# ota.net
KiCad netlist of a schematic drawn in EAGLE
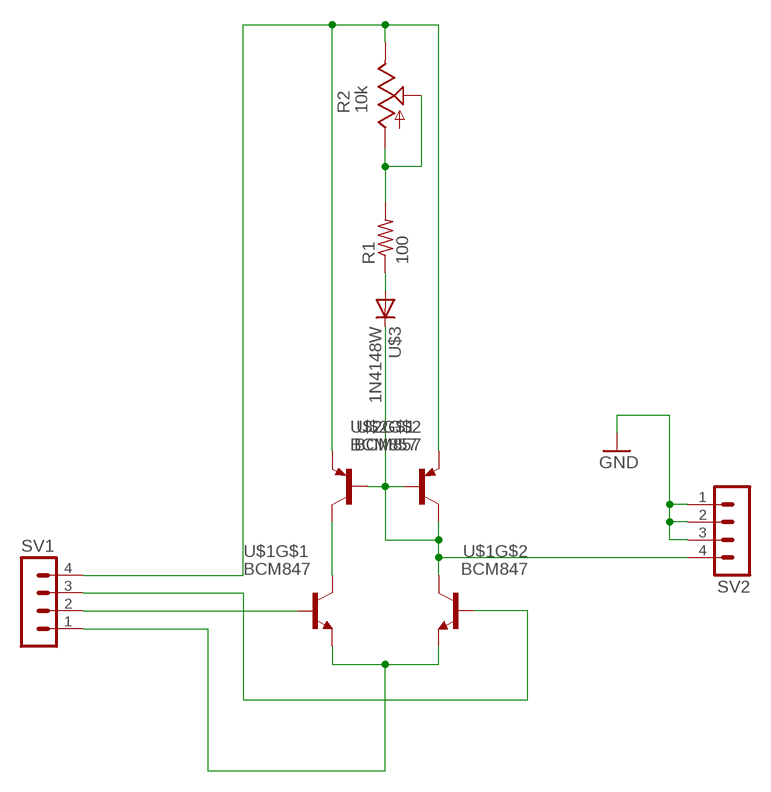
[diagram p0: schematic, sheet 1]

(export (version "E")
  (design (tool "Eeschema 10.0.6"))
  (components
    (comp (ref "R1")
      (value "100")
      (footprint "eagle-import:R0603")
      (libsource (lib "eagle-import") (part "R-US_R0603"))
    )
    (comp (ref "R2")
      (value "10k")
      (footprint "eagle-import:SM-42_43W")
      (libsource (lib "eagle-import") (part "TRIM_US-SM-42/43W"))
    )
    (comp (ref "SV1")
      (value "MA04-1")
      (footprint "eagle-import:MA04-1")
      (libsource (lib "eagle-import") (part "MA04-1"))
    )
    (comp (ref "SV2")
      (value "MA04-1")
      (footprint "eagle-import:MA04-1")
      (libsource (lib "eagle-import") (part "MA04-1"))
    )
    (comp (ref "U$1")
      (value "BCM847")
      (footprint "eagle-import:SOT457R_PHILIPS")
      (libsource (lib "eagle-import") (part "BCM847"))
    )
    (comp (ref "U$2")
      (value "BCM857")
      (footprint "eagle-import:SOT457R_PHILIPS")
      (libsource (lib "eagle-import") (part "BCM857"))
    )
    (comp (ref "U$3")
      (value "1N4148W")
      (footprint "eagle-import:SOD123")
      (libsource (lib "eagle-import") (part "1N4148W"))
    )
  )
  (nets
    (net (code "1") (name "GND") (class "Default")
      (node (ref "SV2") (pin "1") (pinfunction "1_1") (pintype "passive"))
      (node (ref "SV2") (pin "2") (pinfunction "2_2") (pintype "passive"))
      (node (ref "SV2") (pin "3") (pinfunction "3_3") (pintype "passive"))
    )
    (net (code "2") (name "Net-(R1-Pad1)") (class "Default")
      (node (ref "R1") (pin "1") (pinfunction "1_1") (pintype "passive"))
      (node (ref "U$3") (pin "A") (pinfunction "A_A") (pintype "passive"))
    )
    (net (code "3") (name "Net-(R2-A)") (class "Default")
      (node (ref "R1") (pin "2") (pinfunction "2_2") (pintype "passive"))
      (node (ref "R2") (pin "1") (pinfunction "A_1") (pintype "passive"))
      (node (ref "R2") (pin "2") (pinfunction "S_2") (pintype "passive"))
    )
    (net (code "4") (name "Net-(R2-E)") (class "Default")
      (node (ref "R2") (pin "3") (pinfunction "E_3") (pintype "passive"))
      (node (ref "SV1") (pin "4") (pinfunction "4_4") (pintype "passive"))
      (node (ref "U$2") (pin "1") (pinfunction "E_1") (pintype "passive"))
      (node (ref "U$2") (pin "4") (pinfunction "E_4") (pintype "passive"))
    )
    (net (code "5") (name "Net-(U$1A-B)") (class "Default")
      (node (ref "SV1") (pin "2") (pinfunction "2_2") (pintype "passive"))
      (node (ref "U$1") (pin "2") (pinfunction "B_2") (pintype "passive"))
    )
    (net (code "6") (name "Net-(U$1A-C)") (class "Default")
      (node (ref "U$1") (pin "6") (pinfunction "C_6") (pintype "passive"))
      (node (ref "U$2") (pin "3") (pinfunction "C_3") (pintype "passive"))
    )
    (net (code "7") (name "Net-(U$1A-E)") (class "Default")
      (node (ref "SV1") (pin "1") (pinfunction "1_1") (pintype "passive"))
      (node (ref "U$1") (pin "1") (pinfunction "E_1") (pintype "passive"))
      (node (ref "U$1") (pin "4") (pinfunction "E_4") (pintype "passive"))
    )
    (net (code "8") (name "Net-(U$1B-B)") (class "Default")
      (node (ref "SV1") (pin "3") (pinfunction "3_3") (pintype "passive"))
      (node (ref "U$1") (pin "5") (pinfunction "B_5") (pintype "passive"))
    )
    (net (code "9") (name "Net-(U$1B-C)") (class "Default")
      (node (ref "SV2") (pin "4") (pinfunction "4_4") (pintype "passive"))
      (node (ref "U$1") (pin "3") (pinfunction "C_3") (pintype "passive"))
      (node (ref "U$2") (pin "2") (pinfunction "B_2") (pintype "passive"))
      (node (ref "U$2") (pin "5") (pinfunction "B_5") (pintype "passive"))
      (node (ref "U$2") (pin "6") (pinfunction "C_6") (pintype "passive"))
      (node (ref "U$3") (pin "C") (pinfunction "C_C") (pintype "passive"))
    )
  )
)
